# PWR.net
KiCad netlist of a schematic drawn in Altium Designer
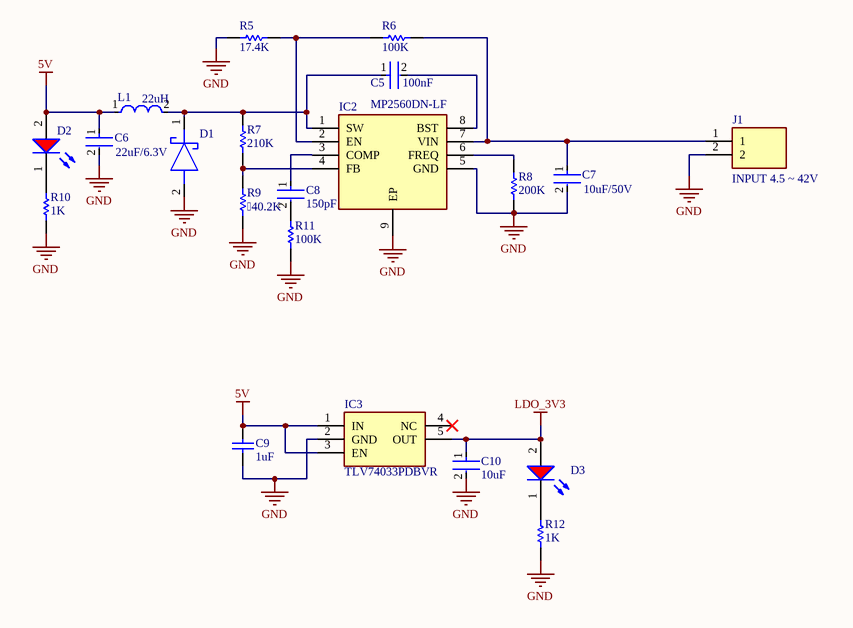
[diagram p0: PWR.SchDoc]

(export (version "E")
  (design (tool "Eeschema 10.0.6"))
  (components
    (comp (ref "C5")
      (value "100nF")
      (footprint "FP-CC0805-0_85-MFG")
      (description "CAP CER 0.1UF 16V X7R 0805")
      (fields
        (field (name "MANUFACTURER PART NUMBER") "CC0805KRX7R7BB104")
        (field (name "MANUFACTURER") "Yageo")
      )
      (libsource (lib "Altium Content Vault") (part "11868f565c42a9108669ba33697ecf6"))
    )
    (comp (ref "C6")
      (value "22uF/6.3V")
      (footprint "FP-GRM21B-0_15-MFG")
      (description "Chip Multilayer Ceramic Capacitors for General Purpose, 0805, 22uF, X5R, 15%, 20%, 6.3V")
      (fields (field (name "VOLTAGE") "6.3V") (field (name "TOLERANCE") "20%"))
      (libsource (lib "Altium Content Vault") (part "b4654b650e69147ec39a6b967a45e02"))
    )
    (comp (ref "C7")
      (value "10uF/50V")
      (footprint "FP-GRM31-0_2-IPC_A")
      (description "CAP CER 10UF 50V X5R 1206")
      (fields
        (field (name "OCTOPART") "https://octopart.com/grm31cr61h106ka12l-murata-18903335")
        (field (name "TOLERANCE") "10%")
      )
      (libsource (lib "Altium Content Vault") (part "11868f565c42a9108669ba33697ecf6"))
    )
    (comp (ref "C8")
      (value "150pF")
      (footprint "FP-0805-L_2_01_0_2-W_1_25-IPC_A")
      (description "General Purpose Ceramic Capacitor, 0805, 150pF, 5%, C0G, 30ppm/°C, 50V")
      (fields (field (name "TOLERANCE") "5%") (field (name "VOLTAGE") "50V"))
      (libsource (lib "Altium Content Vault") (part "02cd4be3c70576c341d710602a673aa"))
    )
    (comp (ref "C9")
      (value "1uF")
      (footprint "CAPC2013X140X50LL20T25")
      (fields (field (name "PART NUMBER") "C0805C105K3RACTU") (field (name "MANUFACTURER") "Kemet"))
      (libsource (lib "Altium Content Vault") (part "CAP"))
    )
    (comp (ref "C10")
      (value "10uF")
      (footprint "FP-GRM21B-0_1-IPC_C")
      (description "Chip Multilayer Ceramic Capacitors for General Purpose, 0805, 10uF, X5R, 15%, 10%, 16V")
      (fields (field (name "TOLERANCE") "10%") (field (name "VOLTAGE") "16V"))
      (libsource (lib "Altium Content Vault") (part "b4654b650e69147ec39a6b967a45e02"))
    )
    (comp (ref "D1")
      (value "SBR2A40P1-7")
      (footprint "SamacSys:POWERDI123_1")
      (description "Schottky Diode")
      (fields (field (name "MOUSER PART NUMBER") "621-SBR2A40P1-7"))
      (libsource (lib "*") (part "SBR2A40P1-7"))
    )
    (comp (ref "D2")
      (value "RED LED")
      (footprint "WL-SMCW_0805_150080xx75000")
      (description "SMD LED 0805")
      (libsource (lib "Altium Content Vault") (part "LED_Red_2A-1K"))
    )
    (comp (ref "D3")
      (value "RED LED")
      (footprint "WL-SMCW_0805_150080xx75000")
      (description "SMD LED 0805")
      (libsource (lib "Altium Content Vault") (part "LED_Red_2A-1K"))
    )
    (comp (ref "IC2")
      (value "MP2560DN-LF")
      (footprint "SamacSys:SOIC127P600X170-9N")
      (description "Integrated Circuit")
      (fields (field (name "MOUSER PART NUMBER") "946-MP2560DNLF"))
      (libsource (lib "*") (part "MP2560DN-LF"))
    )
    (comp (ref "IC3")
      (value "TLV74033PDBVR")
      (footprint "SamacSys:SOT95P280X145-5N")
      (description "Integrated Circuit")
      (fields (field (name "MOUSER PART NUMBER") "595-TLV74033PDBVR"))
      (libsource (lib "*") (part "TLV74033PDBVR"))
    )
    (comp (ref "J1")
      (value "INPUT 4.5 ~ 42V")
      (footprint "SamacSys:1715022")
      (description "Connector")
      (fields
        (field (name "MANUFACTURER_PART_NUMBER") "1715022")
        (field (name "MOUSER PART NUMBER") "651-1715022")
      )
      (libsource (lib "*") (part "1715022"))
    )
    (comp (ref "L1")
      (value "22uH")
      (footprint "FP-SRP6060FA-MFG")
      (description "IND,6.6X6.4X5.8MM,22UH,20%,5A,SH")
      (fields (field (name "TOLERANCE") "20%"))
      (libsource (lib "Altium Content Vault") (part "725321dda6339637d4d059423bc1c3c"))
    )
    (comp (ref "R5")
      (value "17.4K")
      (footprint "RESC2013X50X30NL20T20")
      (fields (field (name "MANUFACTURER") "Vishay Dale") (field (name "PART NUMBER") "CRCW080517K4FKEA"))
      (libsource (lib "Altium Content Vault") (part "RES"))
    )
    (comp (ref "R6")
      (value "100K")
      (footprint "RESC2013X70X40ML20T20")
      (fields (field (name "PART NUMBER") "ERJ-6ENF1003V") (field (name "MANUFACTURER") "Panasonic"))
      (libsource (lib "Altium Content Vault") (part "RES"))
    )
    (comp (ref "R7")
      (value "210K")
      (footprint "RESC2013X50X30LL20T20")
      (fields (field (name "PART NUMBER") "CRCW0805210KFKEA") (field (name "MANUFACTURER") "Vishay Dale"))
      (libsource (lib "Altium Content Vault") (part "RES"))
    )
    (comp (ref "R8")
      (value "200K")
      (footprint "RESC2013X50X30NL20T20")
      (fields (field (name "PART NUMBER") "CRCW0805200KFKEA") (field (name "MANUFACTURER") "Vishay Dale"))
      (libsource (lib "Altium Content Vault") (part "RES"))
    )
    (comp (ref "R9")
      (value "40.2K")
      (footprint "RESC2013X50X30NL20T20")
      (fields (field (name "PART NUMBER") "CRCW080540K2FKEA") (field (name "MANUFACTURER") "Vishay Dale"))
      (libsource (lib "Altium Content Vault") (part "RES"))
    )
    (comp (ref "R10")
      (value "1K")
      (footprint "RESC2013X50X30NL20T20")
      (fields (field (name "PART NUMBER") "CRCW08051K00FKEA") (field (name "MANUFACTURER") "Vishay Dale"))
      (libsource (lib "Altium Content Vault") (part "RES"))
    )
    (comp (ref "R11")
      (value "100K")
      (footprint "RESC2013X70X40ML20T20")
      (fields (field (name "PART NUMBER") "ERJ-6ENF1003V") (field (name "MANUFACTURER") "Panasonic"))
      (libsource (lib "Altium Content Vault") (part "RES"))
    )
    (comp (ref "R12")
      (value "1K")
      (footprint "RESC2013X50X30NL20T20")
      (fields (field (name "PART NUMBER") "CRCW08051K00FKEA") (field (name "MANUFACTURER") "Vishay Dale"))
      (libsource (lib "Altium Content Vault") (part "RES"))
    )
  )
  (nets
    (net (code "1") (name "5V") (class "Default")
      (node (ref "C6") (pin "1") (pinfunction "1_1") (pintype "passive"))
      (node (ref "C9") (pin "2") (pinfunction "2_2") (pintype "passive"))
      (node (ref "D2") (pin "2") (pinfunction "A_2") (pintype "passive"))
      (node (ref "IC3") (pin "1") (pinfunction "IN_1") (pintype "passive"))
      (node (ref "IC3") (pin "3") (pinfunction "EN_3") (pintype "passive"))
      (node (ref "L1") (pin "1") (pinfunction "1_1") (pintype "passive"))
    )
    (net (code "2") (name "GND") (class "Default")
      (node (ref "C10") (pin "2") (pinfunction "2_2") (pintype "passive"))
      (node (ref "C6") (pin "2") (pinfunction "2_2") (pintype "passive"))
      (node (ref "C7") (pin "2") (pinfunction "2_2") (pintype "passive"))
      (node (ref "C9") (pin "1") (pinfunction "1_1") (pintype "passive"))
      (node (ref "D1") (pin "2") (pinfunction "A_2") (pintype "passive"))
      (node (ref "IC2") (pin "5") (pinfunction "GND_5") (pintype "passive"))
      (node (ref "IC2") (pin "9") (pinfunction "EP_9") (pintype "passive"))
      (node (ref "IC3") (pin "2") (pinfunction "GND_2") (pintype "passive"))
      (node (ref "J1") (pin "2") (pinfunction "2_2") (pintype "passive"))
      (node (ref "R10") (pin "1") (pinfunction "1_1") (pintype "passive"))
      (node (ref "R11") (pin "1") (pinfunction "1_1") (pintype "passive"))
      (node (ref "R12") (pin "1") (pinfunction "1_1") (pintype "passive"))
      (node (ref "R5") (pin "1") (pinfunction "1_1") (pintype "passive"))
      (node (ref "R8") (pin "1") (pinfunction "1_1") (pintype "passive"))
      (node (ref "R9") (pin "1") (pinfunction "1_1") (pintype "passive"))
    )
    (net (code "3") (name "LDO_3V3") (class "Default")
      (node (ref "C10") (pin "1") (pinfunction "1_1") (pintype "passive"))
      (node (ref "D3") (pin "2") (pinfunction "A_2") (pintype "passive"))
      (node (ref "IC3") (pin "5") (pinfunction "OUT_5") (pintype "passive"))
    )
    (net (code "4") (name "Net-(C8-Pad2)") (class "Default")
      (node (ref "C8") (pin "2") (pinfunction "2_2") (pintype "passive"))
      (node (ref "R11") (pin "2") (pinfunction "2_2") (pintype "passive"))
    )
    (net (code "5") (name "Net-(D1-K)") (class "Default")
      (node (ref "C5") (pin "1") (pinfunction "1_1") (pintype "passive"))
      (node (ref "D1") (pin "1") (pinfunction "K_1") (pintype "passive"))
      (node (ref "IC2") (pin "1") (pinfunction "SW_1") (pintype "passive"))
      (node (ref "L1") (pin "2") (pinfunction "2_2") (pintype "passive"))
      (node (ref "R7") (pin "2") (pinfunction "2_2") (pintype "passive"))
    )
    (net (code "6") (name "Net-(D2-K)") (class "Default")
      (node (ref "D2") (pin "1") (pinfunction "K_1") (pintype "passive"))
      (node (ref "R10") (pin "2") (pinfunction "2_2") (pintype "passive"))
    )
    (net (code "7") (name "Net-(D3-K)") (class "Default")
      (node (ref "D3") (pin "1") (pinfunction "K_1") (pintype "passive"))
      (node (ref "R12") (pin "2") (pinfunction "2_2") (pintype "passive"))
    )
    (net (code "8") (name "Net-(IC2-BST)") (class "Default")
      (node (ref "C5") (pin "2") (pinfunction "2_2") (pintype "passive"))
      (node (ref "IC2") (pin "8") (pinfunction "BST_8") (pintype "passive"))
    )
    (net (code "9") (name "Net-(IC2-COMP)") (class "Default")
      (node (ref "C8") (pin "1") (pinfunction "1_1") (pintype "passive"))
      (node (ref "IC2") (pin "3") (pinfunction "COMP_3") (pintype "passive"))
    )
    (net (code "10") (name "Net-(IC2-EN)") (class "Default")
      (node (ref "IC2") (pin "2") (pinfunction "EN_2") (pintype "passive"))
      (node (ref "R5") (pin "2") (pinfunction "2_2") (pintype "passive"))
      (node (ref "R6") (pin "1") (pinfunction "1_1") (pintype "passive"))
    )
    (net (code "11") (name "Net-(IC2-FB)") (class "Default")
      (node (ref "IC2") (pin "4") (pinfunction "FB_4") (pintype "passive"))
      (node (ref "R7") (pin "1") (pinfunction "1_1") (pintype "passive"))
      (node (ref "R9") (pin "2") (pinfunction "2_2") (pintype "passive"))
    )
    (net (code "12") (name "Net-(IC2-FREQ)") (class "Default")
      (node (ref "IC2") (pin "6") (pinfunction "FREQ_6") (pintype "passive"))
      (node (ref "R8") (pin "2") (pinfunction "2_2") (pintype "passive"))
    )
    (net (code "13") (name "Net-(IC2-VIN)") (class "Default")
      (node (ref "C7") (pin "1") (pinfunction "1_1") (pintype "passive"))
      (node (ref "IC2") (pin "7") (pinfunction "VIN_7") (pintype "passive"))
      (node (ref "J1") (pin "1") (pinfunction "1_1") (pintype "passive"))
      (node (ref "R6") (pin "2") (pinfunction "2_2") (pintype "passive"))
    )
    (net (code "14") (name "unconnected-(IC3-NC-Pad4)") (class "Default")
      (node (ref "IC3") (pin "4") (pinfunction "NC_4") (pintype "passive+no_connect"))
    )
  )
)
